# Encoder_Sheet1.net
KiCad netlist of a schematic drawn in Altium Designer
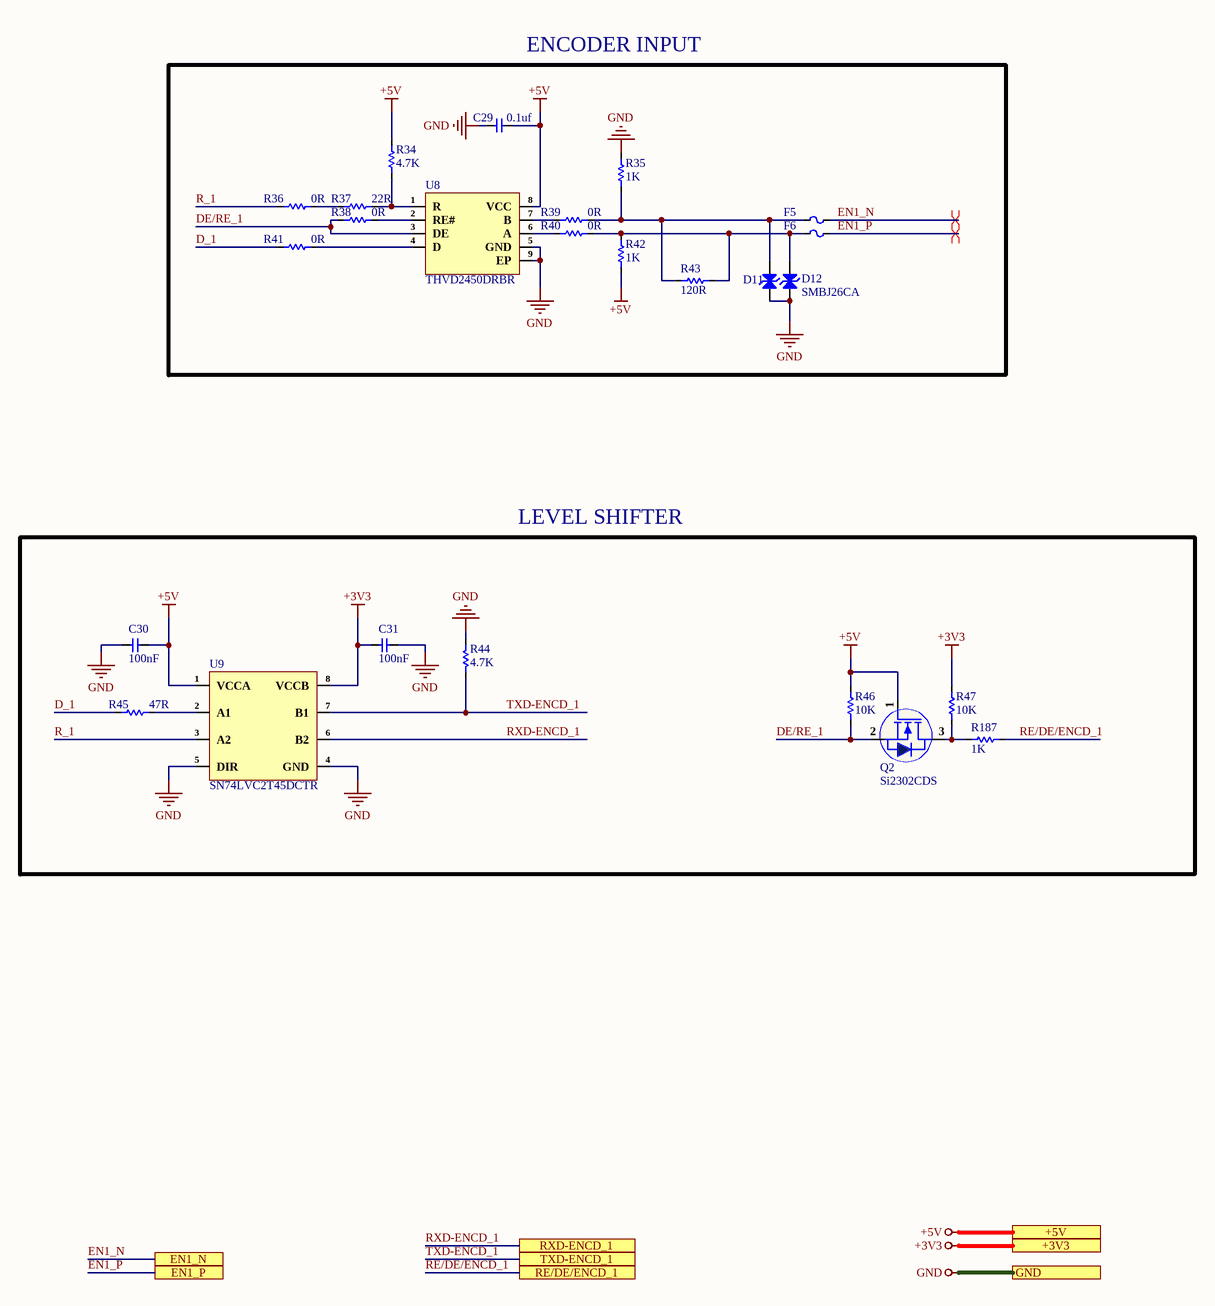
[diagram p0: Encoder_Sheet1.SchDoc]

(export (version "E")
  (design (tool "Eeschema 10.0.6"))
  (components
    (comp (ref "C29")
      (value "0.1uf")
      (footprint "Cap-0402")
      (description "CAP CER 0.1UF 100V X5R 0402")
      (fields
        (field (name "MANUFACTURER") "Murata")
        (field (name "MANUFACTURER PART NUMBER") "GRM155R62A104KE14D")
      )
      (libsource (lib "eSpark Libraries") (part "GRM155R62A104KE14D"))
    )
    (comp (ref "C30")
      (value "100nF")
      (footprint "cap-0402")
      (description "CAP CER 0.1UF 50V X7R 0402")
      (fields
        (field (name "MANUFACTURER") "TDK")
        (field (name "MANUFACTURER PART NUMBER") "C1005X7R1H104KT000F")
      )
      (libsource (lib "eSpark Libraries") (part "C1005X7R1H104KT000F"))
    )
    (comp (ref "C31")
      (value "100nF")
      (footprint "cap-0402")
      (description "CAP CER 0.1UF 50V X7R 0402")
      (fields
        (field (name "MANUFACTURER") "TDK")
        (field (name "MANUFACTURER PART NUMBER") "C1005X7R1H104KT000F")
      )
      (libsource (lib "eSpark Libraries") (part "C1005X7R1H104KT000F"))
    )
    (comp (ref "D11")
      (value "SMBJ26CA")
      (footprint "SMB Bi Directional")
      (description "SMB(DO-214AA) TVS ROHS")
      (fields (field (name "MANUFACTURER") "MSKSEMI") (field (name "LCSC PART NUMBER") "C5331111"))
      (libsource (lib "eSpark Libraries") (part "SMBJ26CA"))
    )
    (comp (ref "D12")
      (value "SMBJ26CA")
      (footprint "SMB Bi Directional")
      (description "SMB(DO-214AA) TVS ROHS")
      (fields (field (name "MANUFACTURER") "MSKSEMI") (field (name "LCSC PART NUMBER") "C5331111"))
      (libsource (lib "eSpark Libraries") (part "SMBJ26CA"))
    )
    (comp (ref "F5")
      (value "SMD0805P020TF")
      (footprint "Fuse-0805")
      (description "9V 200mA 100A 500mA 0805 Resettable Fuses ROHS")
      (fields (field (name "MANUFACTURER") "RUILON") (field (name "LCSC PART NUMBER") "C20976"))
      (libsource (lib "eSpark_centralized_Library(2022)") (part "SMD0805P020TF"))
    )
    (comp (ref "F6")
      (value "SMD0805P020TF")
      (footprint "Fuse-0805")
      (description "9V 200mA 100A 500mA 0805 Resettable Fuses ROHS")
      (fields (field (name "MANUFACTURER") "RUILON") (field (name "LCSC PART NUMBER") "C20976"))
      (libsource (lib "eSpark_centralized_Library(2022)") (part "SMD0805P020TF"))
    )
    (comp (ref "Q2")
      (value "Si2302CDS")
      (footprint "Sot-23")
      (description "N-CHANNEL 20-V (D-S) MOSFET")
      (fields
        (field (name "MANUFACTURER") "TECH PUBLIC")
        (field (name "MANUFACTURER PART NUMBER") "SI2302CDS")
      )
      (libsource (lib "eSpark_centralized_Library(2022)") (part "Si2302CDS"))
    )
    (comp (ref "R34")
      (value "4.7K")
      (footprint "Res-0402")
      (description "RES 4.7K OHM 1% 1/16W 0402")
      (fields
        (field (name "MANUFACTURER") "Yageo")
        (field (name "MANUFACTURER PART NUMBER") "RC0402FR-074K7L")
      )
      (libsource (lib "eSpark Libraries") (part "RC0402FR-074K7L"))
    )
    (comp (ref "R35")
      (value "1K")
      (footprint "Res-0402")
      (description "RES 1K OHM 1% 1/16W 0402")
      (fields
        (field (name "MANUFACTURER") "Yageo")
        (field (name "MANUFACTURER PART NUMBER") "RC0402FR-071KL")
      )
      (libsource (lib "eSpark Libraries") (part "RC0402FR-071KL"))
    )
    (comp (ref "R36")
      (value "0R")
      (footprint "Res-0603")
      (description "RES 0 OHM JUMPER 1/10W 0603")
      (fields
        (field (name "MANUFACTURER") "Yageo")
        (field (name "MANUFACTURER PART NUMBER") "RC0603JR-070RL")
      )
      (libsource (lib "eSpark Libraries") (part "RC0603JR-070RL"))
    )
    (comp (ref "R37")
      (value "22R")
      (footprint "Res-0402")
      (description "RES 22 OHM 1% 1/16W 0402")
      (fields
        (field (name "MANUFACTURER") "Yageo")
        (field (name "MANUFACTURER PART NUMBER") "RC0402FR-0722RL")
      )
      (libsource (lib "eSpark Libraries") (part "RC0402FR-0722RL"))
    )
    (comp (ref "R38")
      (value "0R")
      (footprint "Res-0603")
      (description "RES 0 OHM JUMPER 1/10W 0603")
      (fields
        (field (name "MANUFACTURER") "Yageo")
        (field (name "MANUFACTURER PART NUMBER") "RC0603JR-070RL")
      )
      (libsource (lib "eSpark Libraries") (part "RC0603JR-070RL"))
    )
    (comp (ref "R39")
      (value "0R")
      (footprint "Res-0603")
      (description "RES 0 OHM JUMPER 1/10W 0603")
      (fields
        (field (name "MANUFACTURER") "Yageo")
        (field (name "MANUFACTURER PART NUMBER") "RC0603JR-070RL")
      )
      (libsource (lib "eSpark Libraries") (part "RC0603JR-070RL"))
    )
    (comp (ref "R40")
      (value "0R")
      (footprint "Res-0603")
      (description "RES 0 OHM JUMPER 1/10W 0603")
      (fields
        (field (name "MANUFACTURER") "Yageo")
        (field (name "MANUFACTURER PART NUMBER") "RC0603JR-070RL")
      )
      (libsource (lib "eSpark Libraries") (part "RC0603JR-070RL"))
    )
    (comp (ref "R41")
      (value "0R")
      (footprint "Res-0603")
      (description "RES 0 OHM JUMPER 1/10W 0603")
      (fields
        (field (name "MANUFACTURER") "Yageo")
        (field (name "MANUFACTURER PART NUMBER") "RC0603JR-070RL")
      )
      (libsource (lib "eSpark Libraries") (part "RC0603JR-070RL"))
    )
    (comp (ref "R42")
      (value "1K")
      (footprint "Res-0402")
      (description "RES 1K OHM 1% 1/16W 0402")
      (fields
        (field (name "MANUFACTURER") "Yageo")
        (field (name "MANUFACTURER PART NUMBER") "RC0402FR-071KL")
      )
      (libsource (lib "eSpark Libraries") (part "RC0402FR-071KL"))
    )
    (comp (ref "R43")
      (value "120R")
      (footprint "Res-0402")
      (description "RES 120 OHM 1% 1/16W 0402")
      (fields
        (field (name "MANUFACTURER") "Yageo")
        (field (name "MANUFACTURER PART NUMBER") "RC0402FR-07120RL")
      )
      (libsource (lib "eSpark Libraries") (part "RC0402FR-07120RL"))
    )
    (comp (ref "R44")
      (value "4.7K")
      (footprint "Res-0402")
      (description "RES 4.7K OHM 1% 1/16W 0402")
      (fields
        (field (name "MANUFACTURER") "Yageo")
        (field (name "MANUFACTURER PART NUMBER") "RC0402FR-074K7L")
      )
      (libsource (lib "eSpark Libraries") (part "RC0402FR-074K7L"))
    )
    (comp (ref "R45")
      (value "47R")
      (footprint "Res-0402")
      (description "RES 47 OHM 1% 1/16W 0402")
      (fields
        (field (name "MANUFACTURER") "Yageo")
        (field (name "MANUFACTURER PART NUMBER") "RC0402FR-0747RL")
      )
      (libsource (lib "eSpark Libraries") (part "RC0402FR-0747RL"))
    )
    (comp (ref "R46")
      (value "10K")
      (footprint "Res-0402")
      (description "RES 10K OHM 1% 1/16W 0402")
      (fields
        (field (name "MANUFACTURER") "Yageo")
        (field (name "MANUFACTURER PART NUMBER") "RC0402FR-0710KL")
      )
      (libsource (lib "eSpark_centralized_Library(2022)") (part "RC0402FR-0710KL"))
    )
    (comp (ref "R47")
      (value "10K")
      (footprint "Res-0402")
      (description "RES 10K OHM 1% 1/16W 0402")
      (fields
        (field (name "MANUFACTURER") "Yageo")
        (field (name "MANUFACTURER PART NUMBER") "RC0402FR-0710KL")
      )
      (libsource (lib "eSpark_centralized_Library(2022)") (part "RC0402FR-0710KL"))
    )
    (comp (ref "R187")
      (value "1K")
      (footprint "Res-0603")
      (description "RES SMD 1K OHM 1% 1/10W 0603")
      (fields
        (field (name "MANUFACTURER") "Yageo")
        (field (name "MANUFACTURER PART NUMBER") "RC0603FR-071KL")
      )
      (libsource (lib "eSpark_centralized_Library(2022)") (part "RC0603FR-071KL"))
    )
    (comp (ref "U8")
      (value "THVD2450DRBR")
      (footprint "SON-8-EP(3x3)")
      (description "IC TRANSCEIVER HALF 1/1 8SON")
      (fields (field (name "MANUFACTURER") "Texas Instruments") (field (name "LCSC PART NUMBER") "C2878080"))
      (libsource (lib "eSpark Libraries") (part "THVD2450DRBR"))
    )
    (comp (ref "U9")
      (value "SN74LVC2T45DCTR")
      (footprint "MSOP-8")
      (description "IC TRANSLATOR BIDIRECTIONAL SM8")
      (fields (field (name "LCSC PART NUMBER") "C22672") (field (name "MANUFACTURER") "Texas Instruments"))
      (libsource (lib "eSpark Libraries") (part "SN74LVC2T45DCTR"))
    )
  )
  (nets
    (net (code "1") (name "+3V3") (class "Default")
      (node (ref "C31") (pin "1") (pinfunction "1_1") (pintype "passive"))
      (node (ref "R47") (pin "1") (pinfunction "1_1") (pintype "passive"))
      (node (ref "U9") (pin "8") (pinfunction "VCCB_8") (pintype "passive"))
    )
    (net (code "2") (name "+5V") (class "Default")
      (node (ref "C29") (pin "2") (pinfunction "2_2") (pintype "passive"))
      (node (ref "C30") (pin "1") (pinfunction "1_1") (pintype "passive"))
      (node (ref "Q2") (pin "1") (pinfunction "G_1") (pintype "passive"))
      (node (ref "R34") (pin "2") (pinfunction "2_2") (pintype "passive"))
      (node (ref "R42") (pin "1") (pinfunction "1_1") (pintype "passive"))
      (node (ref "R46") (pin "1") (pinfunction "1_1") (pintype "passive"))
      (node (ref "U8") (pin "8") (pinfunction "VCC_8") (pintype "passive"))
      (node (ref "U9") (pin "1") (pinfunction "VCCA_1") (pintype "passive"))
    )
    (net (code "3") (name "/DE{slash}RE_1") (class "Default")
      (node (ref "Q2") (pin "2") (pinfunction "S_2") (pintype "passive"))
      (node (ref "R38") (pin "1") (pinfunction "1_1") (pintype "passive"))
      (node (ref "R46") (pin "2") (pinfunction "2_2") (pintype "passive"))
      (node (ref "U8") (pin "3") (pinfunction "DE_3") (pintype "passive"))
    )
    (net (code "4") (name "/D_1") (class "Default")
      (node (ref "R41") (pin "1") (pinfunction "1_1") (pintype "passive"))
      (node (ref "R45") (pin "1") (pinfunction "1_1") (pintype "passive"))
    )
    (net (code "5") (name "/EN1_N") (class "Default")
      (node (ref "F5") (pin "2") (pinfunction "2_2") (pintype "passive"))
    )
    (net (code "6") (name "/EN1_P") (class "Default")
      (node (ref "F6") (pin "2") (pinfunction "2_2") (pintype "passive"))
    )
    (net (code "7") (name "/RE{slash}DE{slash}ENCD_1") (class "Default")
      (node (ref "R187") (pin "2") (pinfunction "2_2") (pintype "passive"))
    )
    (net (code "8") (name "/RXD-ENCD_1") (class "Default")
      (node (ref "U9") (pin "6") (pinfunction "B2_6") (pintype "passive"))
    )
    (net (code "9") (name "/R_1") (class "Default")
      (node (ref "R36") (pin "1") (pinfunction "1_1") (pintype "passive"))
      (node (ref "U9") (pin "3") (pinfunction "A2_3") (pintype "passive"))
    )
    (net (code "10") (name "/TXD-ENCD_1") (class "Default")
      (node (ref "R44") (pin "1") (pinfunction "1_1") (pintype "passive"))
      (node (ref "U9") (pin "7") (pinfunction "B1_7") (pintype "passive"))
    )
    (net (code "11") (name "GND") (class "Default")
      (node (ref "C29") (pin "1") (pinfunction "1_1") (pintype "passive"))
      (node (ref "C30") (pin "2") (pinfunction "2_2") (pintype "passive"))
      (node (ref "C31") (pin "2") (pinfunction "2_2") (pintype "passive"))
      (node (ref "D11") (pin "1") (pinfunction "A_1") (pintype "passive"))
      (node (ref "D12") (pin "1") (pinfunction "A_1") (pintype "passive"))
      (node (ref "R35") (pin "2") (pinfunction "2_2") (pintype "passive"))
      (node (ref "R44") (pin "2") (pinfunction "2_2") (pintype "passive"))
      (node (ref "U8") (pin "5") (pinfunction "GND_5") (pintype "passive"))
      (node (ref "U8") (pin "9") (pinfunction "EP_9") (pintype "passive"))
      (node (ref "U9") (pin "4") (pinfunction "GND_4") (pintype "passive"))
      (node (ref "U9") (pin "5") (pinfunction "DIR_5") (pintype "passive"))
    )
    (net (code "12") (name "Net-(D11-K)") (class "Default")
      (node (ref "D11") (pin "2") (pinfunction "K_2") (pintype "passive"))
      (node (ref "F5") (pin "1") (pinfunction "1_1") (pintype "passive"))
      (node (ref "R35") (pin "1") (pinfunction "1_1") (pintype "passive"))
      (node (ref "R39") (pin "2") (pinfunction "2_2") (pintype "passive"))
      (node (ref "R43") (pin "1") (pinfunction "1_1") (pintype "passive"))
    )
    (net (code "13") (name "Net-(D12-K)") (class "Default")
      (node (ref "D12") (pin "2") (pinfunction "K_2") (pintype "passive"))
      (node (ref "F6") (pin "1") (pinfunction "1_1") (pintype "passive"))
      (node (ref "R40") (pin "2") (pinfunction "2_2") (pintype "passive"))
      (node (ref "R42") (pin "2") (pinfunction "2_2") (pintype "passive"))
      (node (ref "R43") (pin "2") (pinfunction "2_2") (pintype "passive"))
    )
    (net (code "14") (name "Net-(Q2-D)") (class "Default")
      (node (ref "Q2") (pin "3") (pinfunction "D_3") (pintype "passive"))
      (node (ref "R187") (pin "1") (pinfunction "1_1") (pintype "passive"))
      (node (ref "R47") (pin "2") (pinfunction "2_2") (pintype "passive"))
    )
    (net (code "15") (name "Net-(R36-Pad2)") (class "Default")
      (node (ref "R36") (pin "2") (pinfunction "2_2") (pintype "passive"))
      (node (ref "R37") (pin "1") (pinfunction "1_1") (pintype "passive"))
    )
    (net (code "16") (name "Net-(U8-A)") (class "Default")
      (node (ref "R40") (pin "1") (pinfunction "1_1") (pintype "passive"))
      (node (ref "U8") (pin "6") (pinfunction "A_6") (pintype "passive"))
    )
    (net (code "17") (name "Net-(U8-B)") (class "Default")
      (node (ref "R39") (pin "1") (pinfunction "1_1") (pintype "passive"))
      (node (ref "U8") (pin "7") (pinfunction "B_7") (pintype "passive"))
    )
    (net (code "18") (name "Net-(U8-D)") (class "Default")
      (node (ref "R41") (pin "2") (pinfunction "2_2") (pintype "passive"))
      (node (ref "U8") (pin "4") (pinfunction "D_4") (pintype "passive"))
    )
    (net (code "19") (name "Net-(U8-R)") (class "Default")
      (node (ref "R34") (pin "1") (pinfunction "1_1") (pintype "passive"))
      (node (ref "R37") (pin "2") (pinfunction "2_2") (pintype "passive"))
      (node (ref "U8") (pin "1") (pinfunction "R_1") (pintype "passive"))
    )
    (net (code "20") (name "Net-(U8-RE#)") (class "Default")
      (node (ref "R38") (pin "2") (pinfunction "2_2") (pintype "passive"))
      (node (ref "U8") (pin "2") (pinfunction "RE#_2") (pintype "passive"))
    )
    (net (code "21") (name "Net-(U9-A1)") (class "Default")
      (node (ref "R45") (pin "2") (pinfunction "2_2") (pintype "passive"))
      (node (ref "U9") (pin "2") (pinfunction "A1_2") (pintype "passive"))
    )
  )
)
